# io.net
KiCad netlist of a schematic drawn in Altium Designer
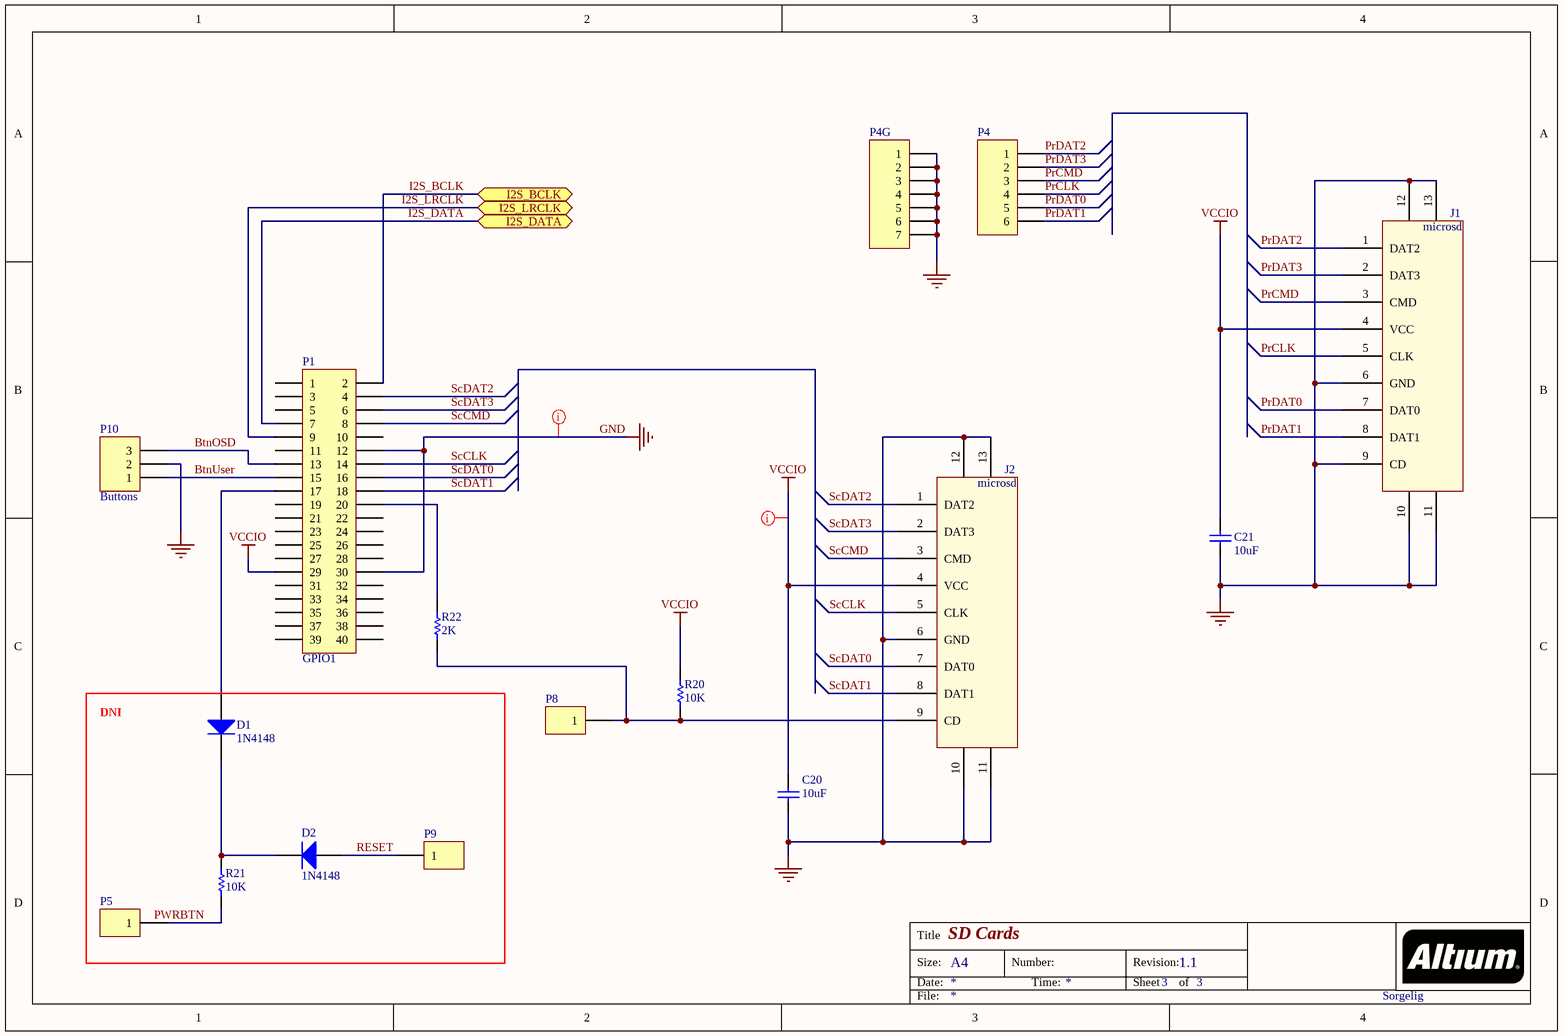
[diagram p0: io.SchDoc]

(export (version "E")
  (design (tool "Eeschema 10.0.6"))
  (components
    (comp (ref "C20")
      (value "10uF")
      (footprint "C0805")
      (description "Ceramic Chip Capacitor - Standard")
      (fields (field (name "Comment") "C0805") (field (name "PUBLISHER") "Altium Limited"))
      (libsource (lib "lib") (part "C0805"))
    )
    (comp (ref "C21")
      (value "10uF")
      (footprint "C0805")
      (description "Ceramic Chip Capacitor - Standard")
      (fields (field (name "Comment") "C0805") (field (name "PUBLISHER") "Altium Limited"))
      (libsource (lib "lib") (part "C0805"))
    )
    (comp (ref "D1")
      (value "1N4148")
      (footprint "DIODE")
      (description "Default Diode")
      (fields (field (name "PUBLISHER") "Altium Limited"))
      (libsource (lib "Miscellaneous Devices") (part "Diode"))
    )
    (comp (ref "D2")
      (value "1N4148")
      (footprint "DIODE")
      (description "Default Diode")
      (fields (field (name "PUBLISHER") "Altium Limited"))
      (libsource (lib "Miscellaneous Devices") (part "Diode"))
    )
    (comp (ref "J1") (value "microsd") (footprint "microsd") (libsource (lib "lib") (part "microsd")))
    (comp (ref "J2") (value "microsd") (footprint "microsd") (libsource (lib "lib") (part "microsd")))
    (comp (ref "P1")
      (value "GPIO1")
      (footprint "HDR20x2")
      (description "Header, 20-Pin, Dual row")
      (fields (field (name "PUBLISHER") "Altium Limited"))
      (libsource (lib "Miscellaneous Connectors") (part "Header 20X2"))
    )
    (comp (ref "P4")
      (value "Header 6")
      (footprint "HDR1X6")
      (description "Header, 6-Pin")
      (fields (field (name "PUBLISHER") "Altium Limited"))
      (libsource (lib "Miscellaneous Connectors") (part "Header 6"))
    )
    (comp (ref "P4G")
      (value "Header 7")
      (footprint "HDR1X7")
      (description "Header, 7-Pin")
      (fields (field (name "PUBLISHER") "Altium Limited"))
      (libsource (lib "Miscellaneous Connectors") (part "Header 7"))
    )
    (comp (ref "P5") (value "Header 1") (footprint "Header 1") (libsource (lib "") (part "Header 1_1")))
    (comp (ref "P8") (value "Header 1") (footprint "Header 1") (libsource (lib "") (part "Header 1_1")))
    (comp (ref "P9") (value "Header 1") (footprint "Header 1") (libsource (lib "lib") (part "Header 1")))
    (comp (ref "P10")
      (value "Buttons")
      (footprint "HDR1X3")
      (description "Header, 3-Pin")
      (fields (field (name "PUBLISHER") "Altium Limited"))
      (libsource (lib "Miscellaneous Connectors") (part "Header 3"))
    )
    (comp (ref "R20")
      (value "10K")
      (footprint "R0805")
      (fields (field (name "PUBLISHER") "Altium Limited"))
      (libsource (lib "lib") (part "R0805"))
    )
    (comp (ref "R21")
      (value "10K")
      (footprint "R0805")
      (fields (field (name "PUBLISHER") "Altium Limited"))
      (libsource (lib "lib") (part "R0805"))
    )
    (comp (ref "R22")
      (value "2K")
      (footprint "R0805")
      (fields (field (name "PUBLISHER") "Altium Limited"))
      (libsource (lib "lib") (part "R0805"))
    )
  )
  (nets
    (net (code "1") (name "/BtnOSD") (class "Default")
      (node (ref "P1") (pin "13") (pinfunction "13_13") (pintype "passive"))
      (node (ref "P10") (pin "3") (pinfunction "3_3") (pintype "passive"))
    )
    (net (code "2") (name "/BtnUser") (class "Default")
      (node (ref "P1") (pin "15") (pinfunction "15_15") (pintype "passive"))
      (node (ref "P10") (pin "1") (pinfunction "1_1") (pintype "passive"))
    )
    (net (code "3") (name "/I2S_BCLK") (class "Default")
      (node (ref "P1") (pin "2") (pinfunction "2_2") (pintype "passive"))
    )
    (net (code "4") (name "/I2S_DATA") (class "Default")
      (node (ref "P1") (pin "7") (pinfunction "7_7") (pintype "passive"))
    )
    (net (code "5") (name "/I2S_LRCLK") (class "Default")
      (node (ref "P1") (pin "9") (pinfunction "9_9") (pintype "passive"))
    )
    (net (code "7") (name "/PrCLK") (class "Default")
      (node (ref "J1") (pin "5") (pinfunction "CLK_5") (pintype "passive"))
      (node (ref "P4") (pin "4") (pinfunction "4_4") (pintype "passive"))
    )
    (net (code "8") (name "/PrCMD") (class "Default")
      (node (ref "J1") (pin "3") (pinfunction "CMD_3") (pintype "passive"))
      (node (ref "P4") (pin "3") (pinfunction "3_3") (pintype "passive"))
    )
    (net (code "9") (name "/PrDAT0") (class "Default")
      (node (ref "J1") (pin "7") (pinfunction "DAT0_7") (pintype "passive"))
      (node (ref "P4") (pin "5") (pinfunction "5_5") (pintype "passive"))
    )
    (net (code "10") (name "/PrDAT1") (class "Default")
      (node (ref "J1") (pin "8") (pinfunction "DAT1_8") (pintype "passive"))
      (node (ref "P4") (pin "6") (pinfunction "6_6") (pintype "passive"))
    )
    (net (code "11") (name "/PrDAT2") (class "Default")
      (node (ref "J1") (pin "1") (pinfunction "DAT2_1") (pintype "passive"))
      (node (ref "P4") (pin "1") (pinfunction "1_1") (pintype "passive"))
    )
    (net (code "12") (name "/PrDAT3") (class "Default")
      (node (ref "J1") (pin "2") (pinfunction "DAT3_2") (pintype "passive"))
      (node (ref "P4") (pin "2") (pinfunction "2_2") (pintype "passive"))
    )
    (net (code "13") (name "/RESET") (class "Default")
      (node (ref "D2") (pin "1") (pinfunction "A_1") (pintype "passive"))
      (node (ref "P9") (pin "1") (pinfunction "1_1") (pintype "passive"))
    )
    (net (code "14") (name "/ScCLK") (class "Default")
      (node (ref "J2") (pin "5") (pinfunction "CLK_5") (pintype "passive"))
      (node (ref "P1") (pin "14") (pinfunction "14_14") (pintype "passive"))
    )
    (net (code "15") (name "/ScCMD") (class "Default")
      (node (ref "J2") (pin "3") (pinfunction "CMD_3") (pintype "passive"))
      (node (ref "P1") (pin "8") (pinfunction "8_8") (pintype "passive"))
    )
    (net (code "16") (name "/ScDAT0") (class "Default")
      (node (ref "J2") (pin "7") (pinfunction "DAT0_7") (pintype "passive"))
      (node (ref "P1") (pin "16") (pinfunction "16_16") (pintype "passive"))
    )
    (net (code "17") (name "/ScDAT1") (class "Default")
      (node (ref "J2") (pin "8") (pinfunction "DAT1_8") (pintype "passive"))
      (node (ref "P1") (pin "18") (pinfunction "18_18") (pintype "passive"))
    )
    (net (code "18") (name "/ScDAT2") (class "Default")
      (node (ref "J2") (pin "1") (pinfunction "DAT2_1") (pintype "passive"))
      (node (ref "P1") (pin "4") (pinfunction "4_4") (pintype "passive"))
    )
    (net (code "19") (name "/ScDAT3") (class "Default")
      (node (ref "J2") (pin "2") (pinfunction "DAT3_2") (pintype "passive"))
      (node (ref "P1") (pin "6") (pinfunction "6_6") (pintype "passive"))
    )
    (net (code "20") (name "GND") (class "Default")
      (node (ref "C20") (pin "1") (pinfunction "1_1") (pintype "passive"))
      (node (ref "C21") (pin "1") (pinfunction "1_1") (pintype "passive"))
      (node (ref "J1") (pin "10") (pinfunction "GND_10") (pintype "passive"))
      (node (ref "J1") (pin "11") (pinfunction "GND_11") (pintype "passive"))
      (node (ref "J1") (pin "12") (pinfunction "GND_12") (pintype "passive"))
      (node (ref "J1") (pin "13") (pinfunction "GND_13") (pintype "passive"))
      (node (ref "J1") (pin "6") (pinfunction "GND_6") (pintype "passive"))
      (node (ref "J1") (pin "9") (pinfunction "CD_9") (pintype "passive"))
      (node (ref "J2") (pin "10") (pinfunction "GND_10") (pintype "passive"))
      (node (ref "J2") (pin "11") (pinfunction "GND_11") (pintype "passive"))
      (node (ref "J2") (pin "12") (pinfunction "GND_12") (pintype "passive"))
      (node (ref "J2") (pin "13") (pinfunction "GND_13") (pintype "passive"))
      (node (ref "J2") (pin "6") (pinfunction "GND_6") (pintype "passive"))
      (node (ref "P1") (pin "12") (pinfunction "12_12") (pintype "passive"))
      (node (ref "P1") (pin "30") (pinfunction "30_30") (pintype "passive"))
      (node (ref "P10") (pin "2") (pinfunction "2_2") (pintype "passive"))
      (node (ref "P4G") (pin "1") (pinfunction "1_1") (pintype "passive"))
      (node (ref "P4G") (pin "2") (pinfunction "2_2") (pintype "passive"))
      (node (ref "P4G") (pin "3") (pinfunction "3_3") (pintype "passive"))
      (node (ref "P4G") (pin "4") (pinfunction "4_4") (pintype "passive"))
      (node (ref "P4G") (pin "5") (pinfunction "5_5") (pintype "passive"))
      (node (ref "P4G") (pin "6") (pinfunction "6_6") (pintype "passive"))
      (node (ref "P4G") (pin "7") (pinfunction "7_7") (pintype "passive"))
    )
    (net (code "21") (name "Net-(D1-A)") (class "Default")
      (node (ref "D1") (pin "1") (pinfunction "A_1") (pintype "passive"))
      (node (ref "P1") (pin "17") (pinfunction "17_17") (pintype "passive"))
    )
    (net (code "22") (name "Net-(D1-K)") (class "Default")
      (node (ref "D1") (pin "2") (pinfunction "K_2") (pintype "passive"))
      (node (ref "D2") (pin "2") (pinfunction "K_2") (pintype "passive"))
      (node (ref "R21") (pin "1") (pinfunction "1_1") (pintype "passive"))
    )
    (net (code "23") (name "Net-(J2-CD)") (class "Default")
      (node (ref "J2") (pin "9") (pinfunction "CD_9") (pintype "passive"))
      (node (ref "P8") (pin "1") (pinfunction "1_1") (pintype "passive"))
      (node (ref "R20") (pin "1") (pinfunction "1_1") (pintype "passive"))
      (node (ref "R22") (pin "1") (pinfunction "1_1") (pintype "passive"))
    )
    (net (code "24") (name "Net-(P1-Pad20)") (class "Default")
      (node (ref "P1") (pin "20") (pinfunction "20_20") (pintype "passive"))
      (node (ref "R22") (pin "2") (pinfunction "2_2") (pintype "passive"))
    )
    (net (code "25") (name "Net-(P5-Pad1)") (class "Default")
      (node (ref "P5") (pin "1") (pinfunction "1_1") (pintype "passive"))
      (node (ref "R21") (pin "2") (pinfunction "2_2") (pintype "passive"))
    )
    (net (code "26") (name "VCCIO") (class "Default")
      (node (ref "C20") (pin "2") (pinfunction "2_2") (pintype "passive"))
      (node (ref "C21") (pin "2") (pinfunction "2_2") (pintype "passive"))
      (node (ref "J1") (pin "4") (pinfunction "VCC_4") (pintype "power_in"))
      (node (ref "J2") (pin "4") (pinfunction "VCC_4") (pintype "power_in"))
      (node (ref "P1") (pin "29") (pinfunction "29_29") (pintype "passive"))
      (node (ref "R20") (pin "2") (pinfunction "2_2") (pintype "passive"))
    )
    (net (code "27") (name "unconnected-(P1-Pad1)") (class "Default")
      (node (ref "P1") (pin "1") (pinfunction "1_1") (pintype "passive"))
    )
    (net (code "28") (name "unconnected-(P1-Pad3)") (class "Default")
      (node (ref "P1") (pin "3") (pinfunction "3_3") (pintype "passive"))
    )
    (net (code "29") (name "unconnected-(P1-Pad5)") (class "Default")
      (node (ref "P1") (pin "5") (pinfunction "5_5") (pintype "passive"))
    )
    (net (code "30") (name "unconnected-(P1-Pad10)") (class "Default")
      (node (ref "P1") (pin "10") (pinfunction "10_10") (pintype "passive"))
    )
    (net (code "31") (name "unconnected-(P1-Pad11)") (class "Default")
      (node (ref "P1") (pin "11") (pinfunction "11_11") (pintype "passive"))
    )
    (net (code "32") (name "unconnected-(P1-Pad19)") (class "Default")
      (node (ref "P1") (pin "19") (pinfunction "19_19") (pintype "passive"))
    )
    (net (code "33") (name "unconnected-(P1-Pad21)") (class "Default")
      (node (ref "P1") (pin "21") (pinfunction "21_21") (pintype "passive"))
    )
    (net (code "34") (name "unconnected-(P1-Pad22)") (class "Default")
      (node (ref "P1") (pin "22") (pinfunction "22_22") (pintype "passive"))
    )
    (net (code "35") (name "unconnected-(P1-Pad23)") (class "Default")
      (node (ref "P1") (pin "23") (pinfunction "23_23") (pintype "passive"))
    )
    (net (code "36") (name "unconnected-(P1-Pad24)") (class "Default")
      (node (ref "P1") (pin "24") (pinfunction "24_24") (pintype "passive"))
    )
    (net (code "37") (name "unconnected-(P1-Pad25)") (class "Default")
      (node (ref "P1") (pin "25") (pinfunction "25_25") (pintype "passive"))
    )
    (net (code "38") (name "unconnected-(P1-Pad26)") (class "Default")
      (node (ref "P1") (pin "26") (pinfunction "26_26") (pintype "passive"))
    )
    (net (code "39") (name "unconnected-(P1-Pad27)") (class "Default")
      (node (ref "P1") (pin "27") (pinfunction "27_27") (pintype "passive"))
    )
    (net (code "40") (name "unconnected-(P1-Pad28)") (class "Default")
      (node (ref "P1") (pin "28") (pinfunction "28_28") (pintype "passive"))
    )
    (net (code "41") (name "unconnected-(P1-Pad31)") (class "Default")
      (node (ref "P1") (pin "31") (pinfunction "31_31") (pintype "passive"))
    )
    (net (code "42") (name "unconnected-(P1-Pad32)") (class "Default")
      (node (ref "P1") (pin "32") (pinfunction "32_32") (pintype "passive"))
    )
    (net (code "43") (name "unconnected-(P1-Pad33)") (class "Default")
      (node (ref "P1") (pin "33") (pinfunction "33_33") (pintype "passive"))
    )
    (net (code "44") (name "unconnected-(P1-Pad34)") (class "Default")
      (node (ref "P1") (pin "34") (pinfunction "34_34") (pintype "passive"))
    )
    (net (code "45") (name "unconnected-(P1-Pad35)") (class "Default")
      (node (ref "P1") (pin "35") (pinfunction "35_35") (pintype "passive"))
    )
    (net (code "46") (name "unconnected-(P1-Pad36)") (class "Default")
      (node (ref "P1") (pin "36") (pinfunction "36_36") (pintype "passive"))
    )
    (net (code "47") (name "unconnected-(P1-Pad37)") (class "Default")
      (node (ref "P1") (pin "37") (pinfunction "37_37") (pintype "passive"))
    )
    (net (code "48") (name "unconnected-(P1-Pad38)") (class "Default")
      (node (ref "P1") (pin "38") (pinfunction "38_38") (pintype "passive"))
    )
    (net (code "49") (name "unconnected-(P1-Pad39)") (class "Default")
      (node (ref "P1") (pin "39") (pinfunction "39_39") (pintype "passive"))
    )
    (net (code "50") (name "unconnected-(P1-Pad40)") (class "Default")
      (node (ref "P1") (pin "40") (pinfunction "40_40") (pintype "passive"))
    )
  )
)
